# opampStone-v1.net
KiCad netlist of a schematic drawn in EAGLE
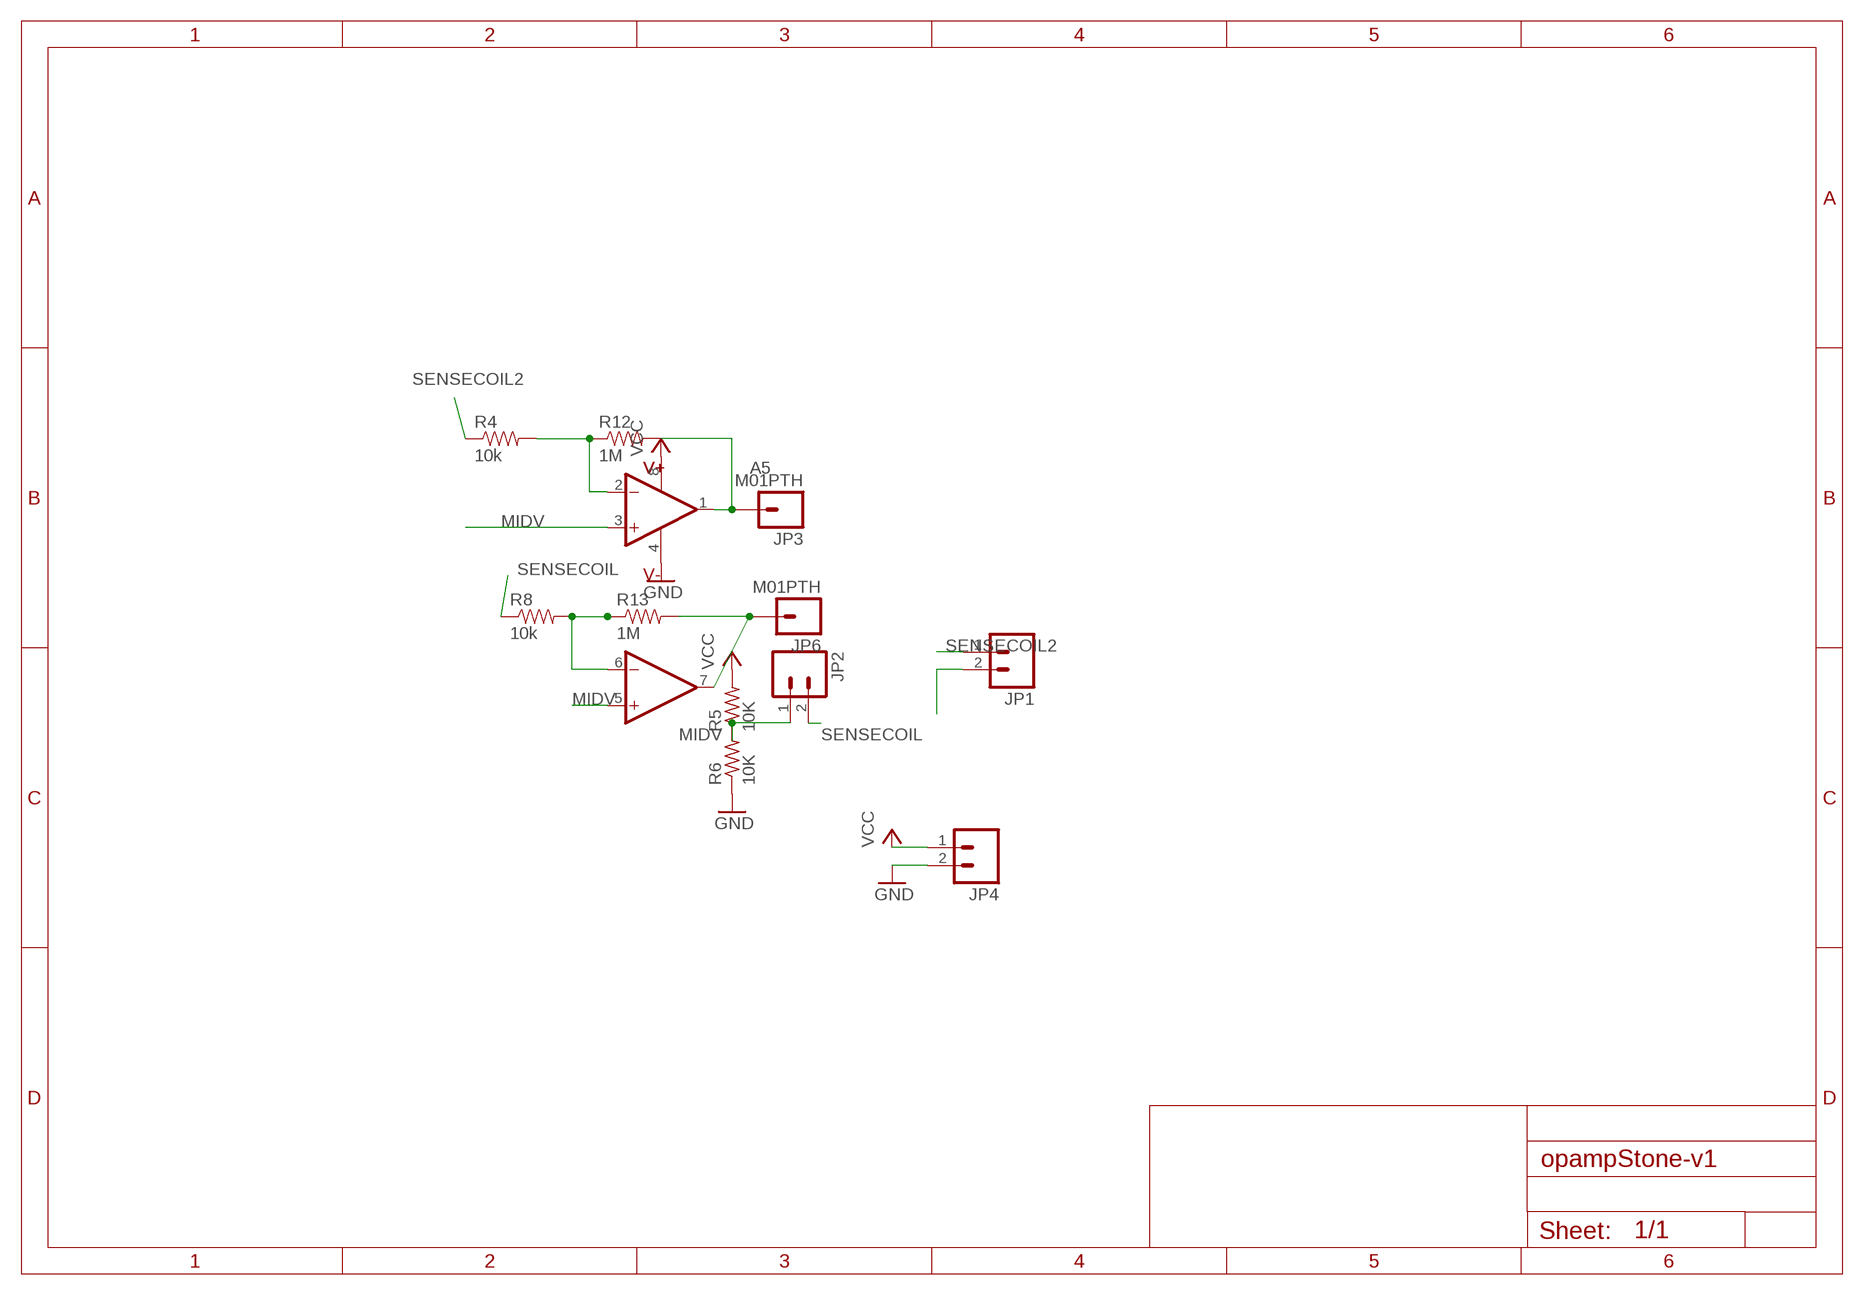
[diagram p0: schematic, sheet 1]

(export (version "E")
  (design (tool "Eeschema 10.0.6"))
  (components
    (comp (ref "JP1")
      (value "M02PTH")
      (footprint "eagle-import:1X02")
      (libsource (lib "eagle-import") (part "M02PTH"))
    )
    (comp (ref "JP2")
      (value "M02PTH")
      (footprint "eagle-import:1X02")
      (libsource (lib "eagle-import") (part "M02PTH"))
    )
    (comp (ref "JP3")
      (value "M01PTH")
      (footprint "eagle-import:1X01")
      (libsource (lib "eagle-import") (part "M01PTH"))
    )
    (comp (ref "JP4")
      (value "M02PTH")
      (footprint "eagle-import:1X02")
      (libsource (lib "eagle-import") (part "M02PTH"))
    )
    (comp (ref "JP6")
      (value "M01PTH")
      (footprint "eagle-import:1X01")
      (libsource (lib "eagle-import") (part "M01PTH"))
    )
    (comp (ref "R4")
      (value "10k")
      (footprint "eagle-import:0603-RES")
      (libsource (lib "eagle-import") (part "RESISTOR0603"))
    )
    (comp (ref "R5")
      (value "10K")
      (footprint "eagle-import:R0603")
      (libsource (lib "eagle-import") (part "R-US_R0603"))
    )
    (comp (ref "R6")
      (value "10K")
      (footprint "eagle-import:R0603")
      (libsource (lib "eagle-import") (part "R-US_R0603"))
    )
    (comp (ref "R8")
      (value "10k")
      (footprint "eagle-import:0603-RES")
      (libsource (lib "eagle-import") (part "RESISTOR0603"))
    )
    (comp (ref "R12")
      (value "1M")
      (footprint "eagle-import:0805")
      (libsource (lib "eagle-import") (part "RESISTOR0805-RES"))
    )
    (comp (ref "R13")
      (value "1M")
      (footprint "eagle-import:0805")
      (libsource (lib "eagle-import") (part "RESISTOR0805-RES"))
    )
    (comp (ref "U2")
      (value "MCP6242")
      (footprint "eagle-import:8-SOIC")
      (libsource (lib "eagle-import") (part "MCP6242"))
    )
  )
  (nets
    (net (code "1") (name "/A5") (class "Default")
      (node (ref "JP3") (pin "1") (pinfunction "1_1") (pintype "passive"))
      (node (ref "R12") (pin "2") (pinfunction "2_2") (pintype "passive"))
      (node (ref "U2") (pin "1") (pinfunction "OUTA_1") (pintype "output"))
    )
    (net (code "2") (name "/MIDV") (class "Default")
      (node (ref "JP1") (pin "2") (pinfunction "2_2") (pintype "passive"))
      (node (ref "JP2") (pin "1") (pinfunction "1_1") (pintype "passive"))
      (node (ref "R5") (pin "1") (pinfunction "1_1") (pintype "passive"))
      (node (ref "R6") (pin "2") (pinfunction "2_2") (pintype "passive"))
      (node (ref "U2") (pin "3") (pinfunction "+INA_3") (pintype "input"))
      (node (ref "U2") (pin "5") (pinfunction "+INB_5") (pintype "input"))
    )
    (net (code "3") (name "/SENSECOIL") (class "Default")
      (node (ref "JP2") (pin "2") (pinfunction "2_2") (pintype "passive"))
      (node (ref "R8") (pin "1") (pinfunction "1_1") (pintype "passive"))
    )
    (net (code "4") (name "/SENSECOIL2") (class "Default")
      (node (ref "JP1") (pin "1") (pinfunction "1_1") (pintype "passive"))
      (node (ref "R4") (pin "1") (pinfunction "1_1") (pintype "passive"))
    )
    (net (code "5") (name "GND") (class "Default")
      (node (ref "JP4") (pin "2") (pinfunction "2_2") (pintype "passive"))
      (node (ref "R6") (pin "1") (pinfunction "1_1") (pintype "passive"))
      (node (ref "U2") (pin "4") (pinfunction "V-_4") (pintype "power_in"))
    )
    (net (code "6") (name "Net-(U2--INA)") (class "Default")
      (node (ref "R12") (pin "1") (pinfunction "1_1") (pintype "passive"))
      (node (ref "R4") (pin "2") (pinfunction "2_2") (pintype "passive"))
      (node (ref "U2") (pin "2") (pinfunction "-INA_2") (pintype "input"))
    )
    (net (code "7") (name "Net-(U2--INB)") (class "Default")
      (node (ref "R13") (pin "1") (pinfunction "1_1") (pintype "passive"))
      (node (ref "R8") (pin "2") (pinfunction "2_2") (pintype "passive"))
      (node (ref "U2") (pin "6") (pinfunction "-INB_6") (pintype "input"))
    )
    (net (code "8") (name "Net-(U2-OUTB)") (class "Default")
      (node (ref "JP6") (pin "1") (pinfunction "1_1") (pintype "passive"))
      (node (ref "R13") (pin "2") (pinfunction "2_2") (pintype "passive"))
      (node (ref "U2") (pin "7") (pinfunction "OUTB_7") (pintype "output"))
    )
    (net (code "9") (name "VCC") (class "Default")
      (node (ref "JP4") (pin "1") (pinfunction "1_1") (pintype "passive"))
      (node (ref "R5") (pin "2") (pinfunction "2_2") (pintype "passive"))
      (node (ref "U2") (pin "8") (pinfunction "V+_8") (pintype "power_in"))
    )
  )
)
